# SCH_MIW_PS_on_PCB_2022-01-19.net
KiCad netlist of a schematic drawn in EasyEDA
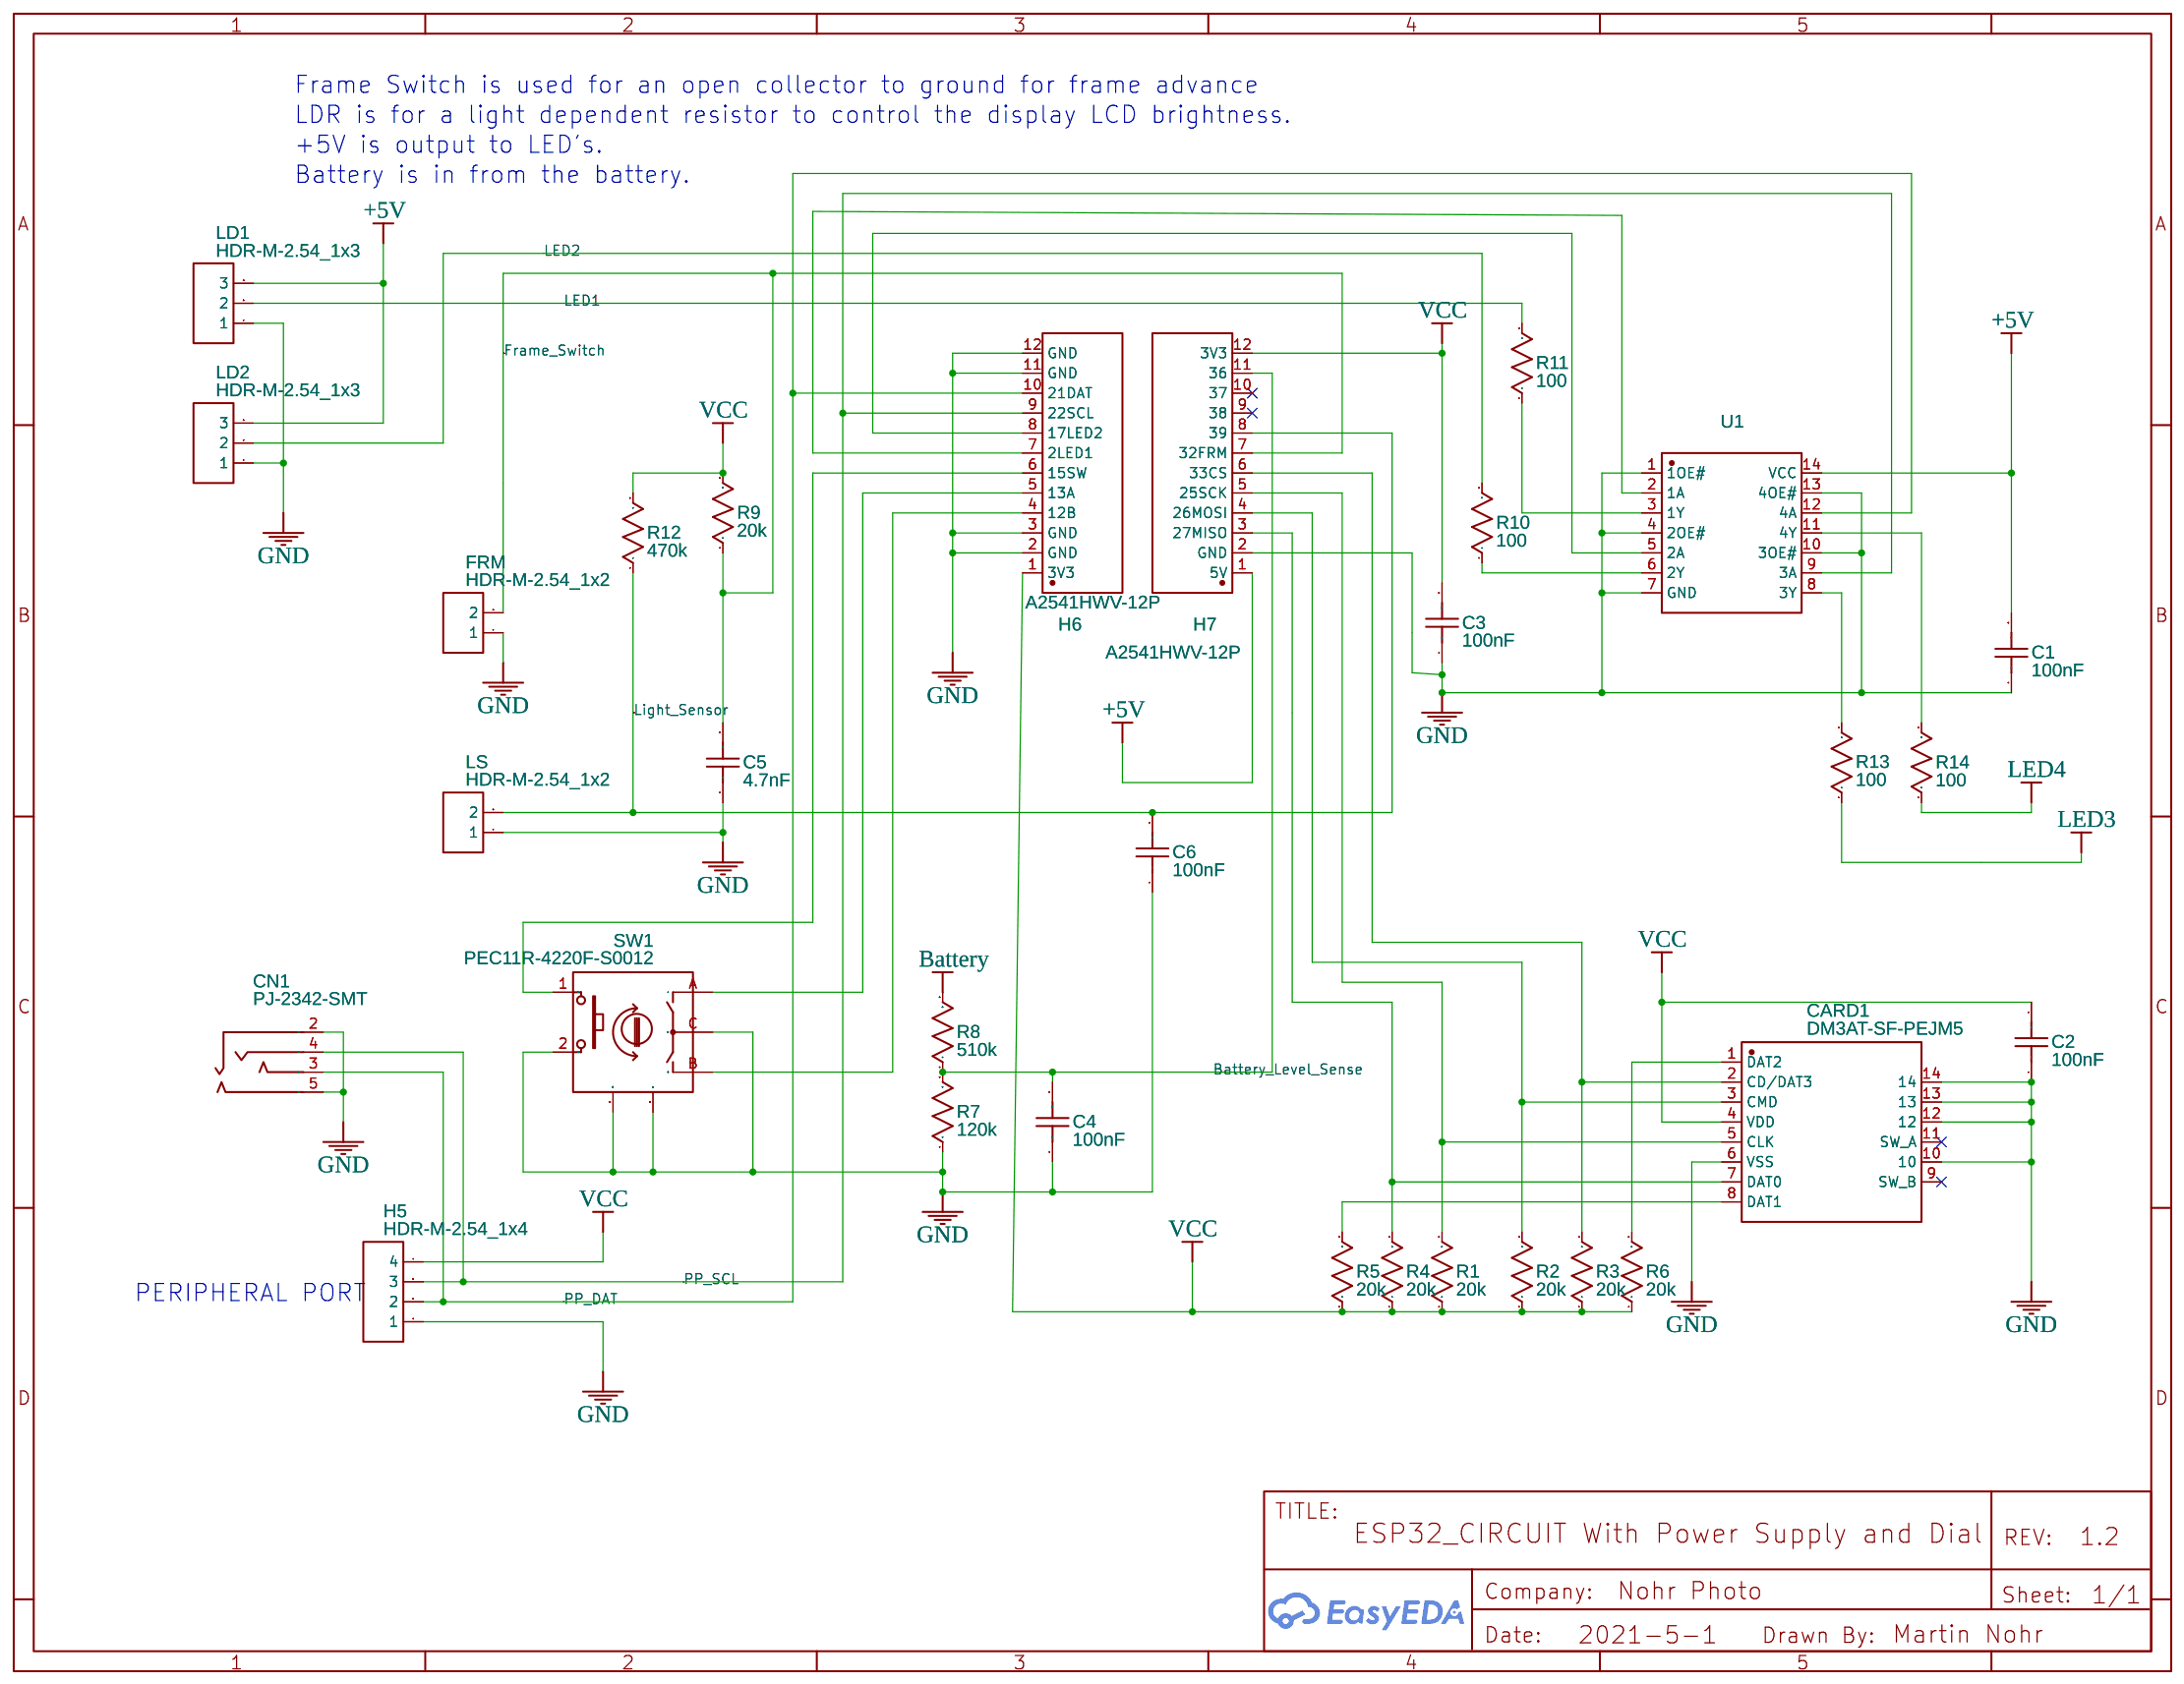
[diagram p0: TTGO_CIRCUIT_PCB_UNIFIED]
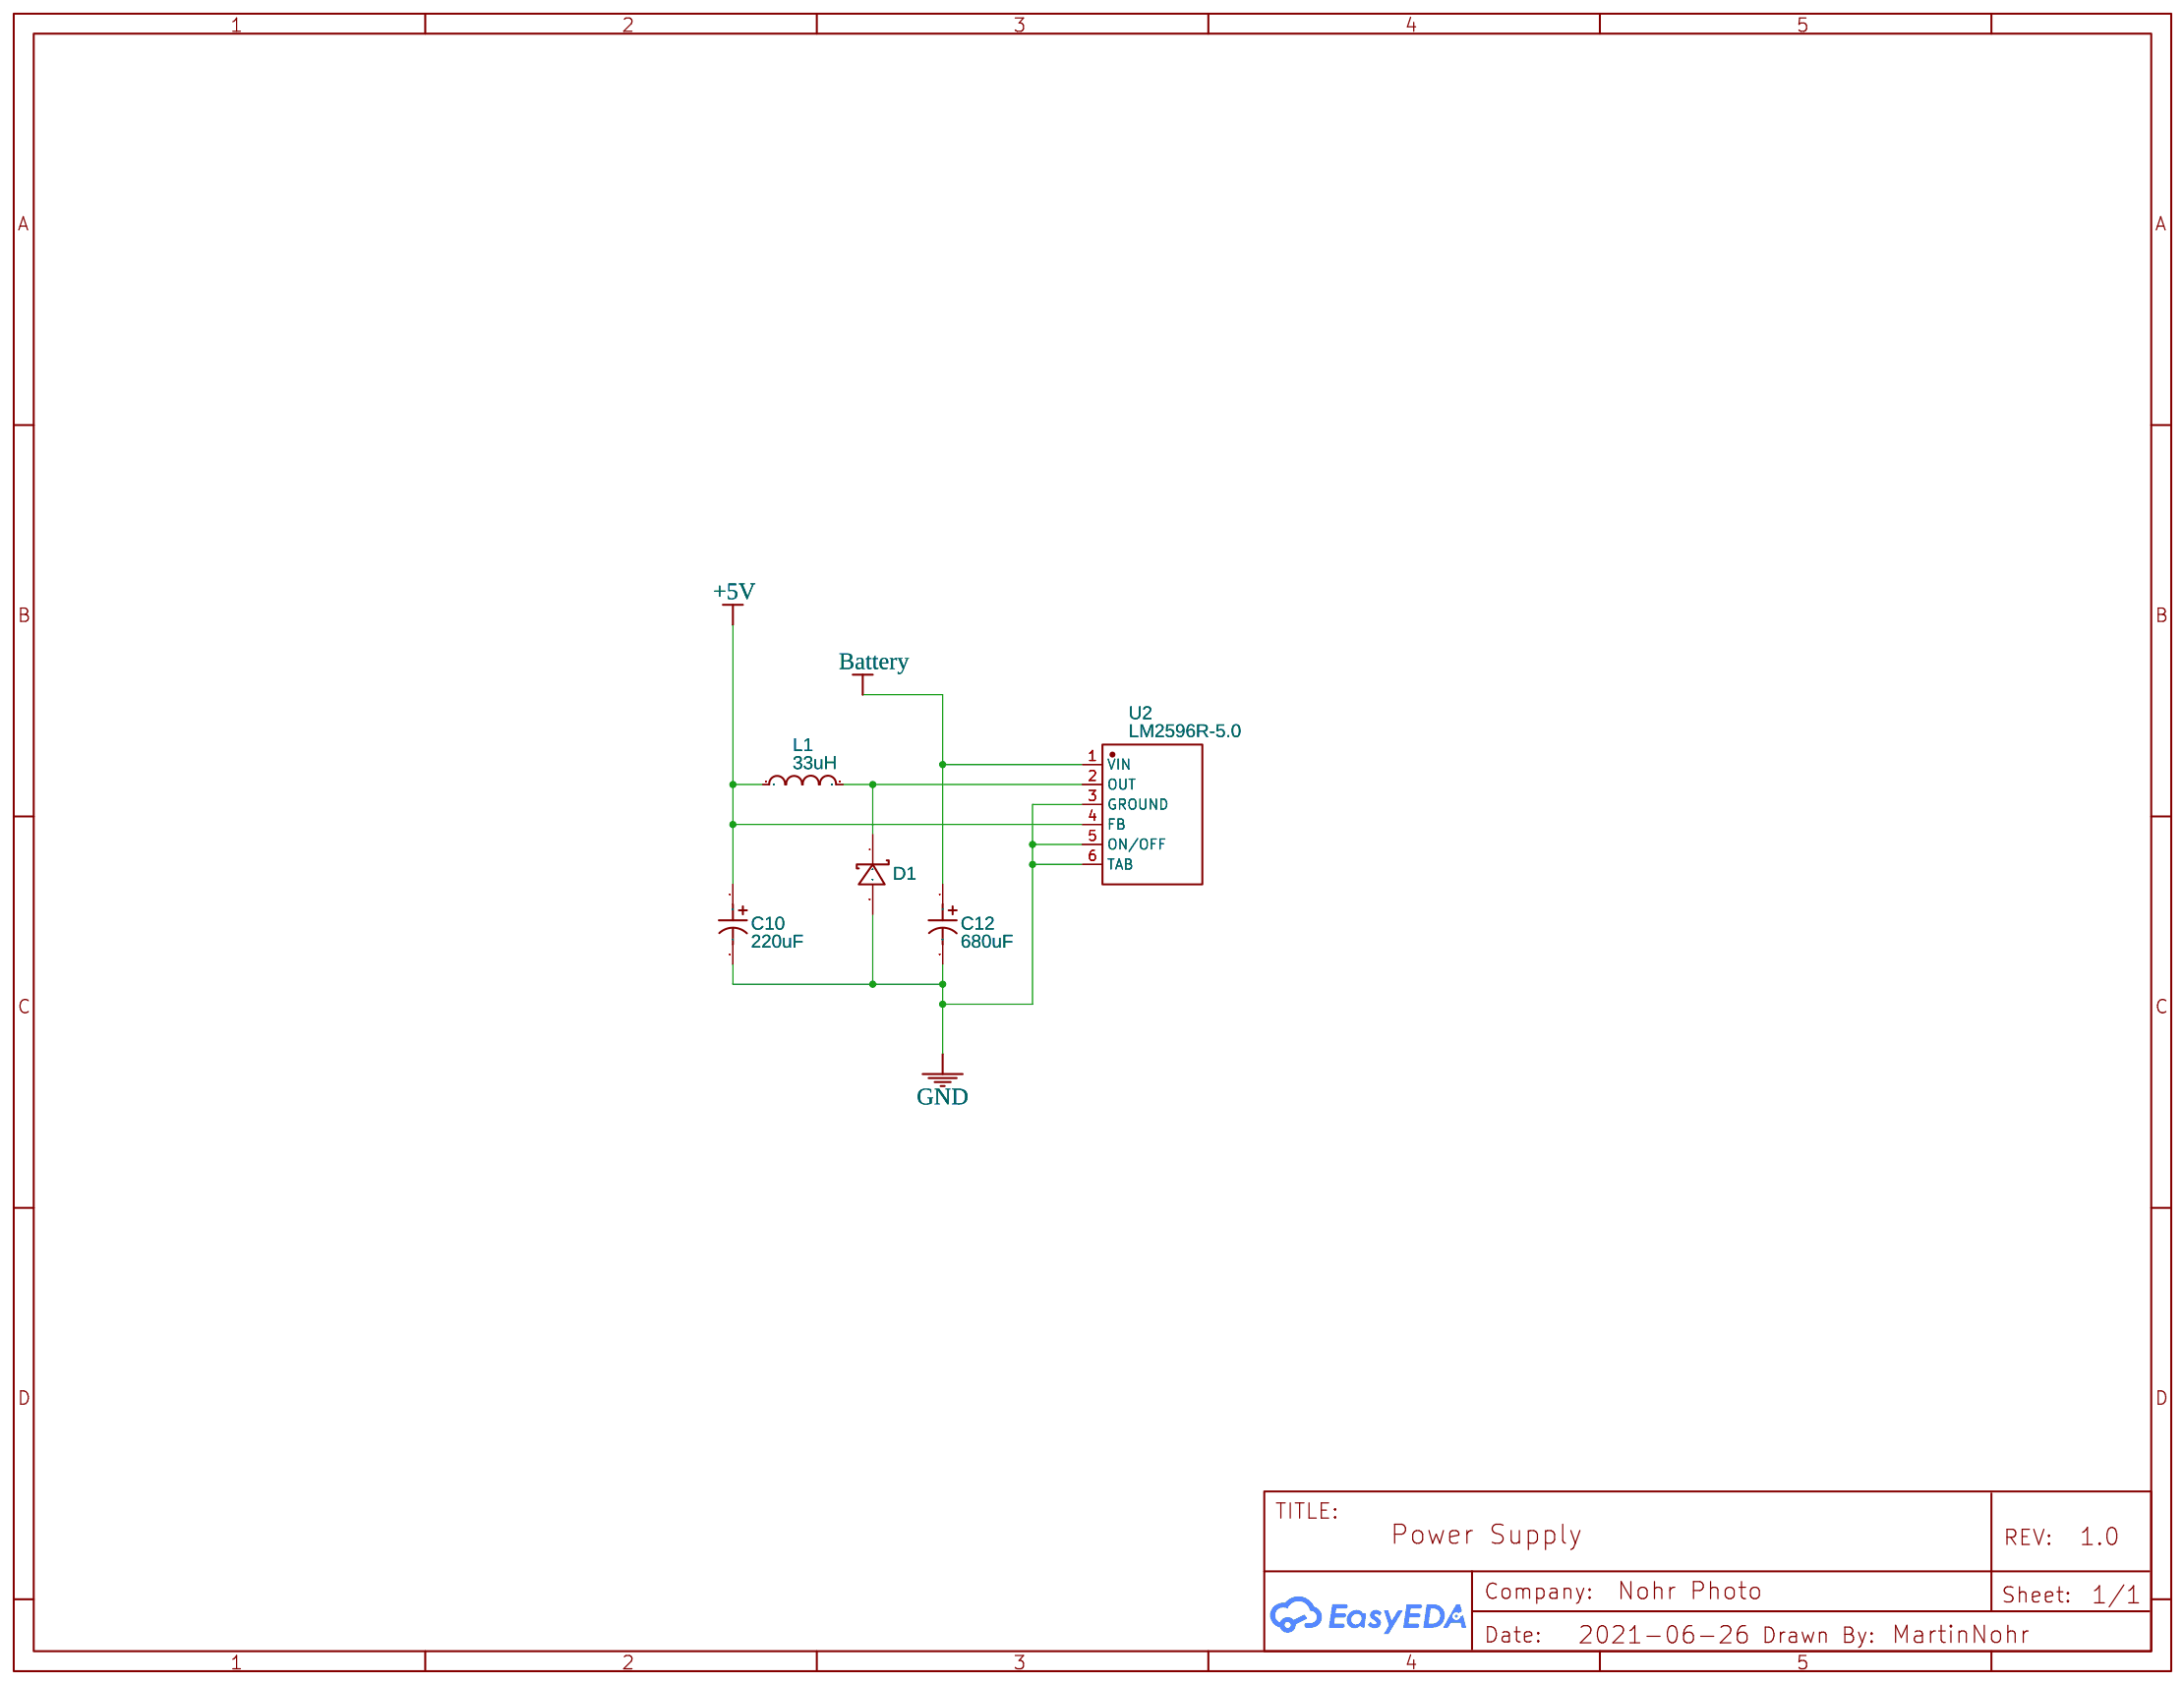
[diagram p1: Power Supply Circuit]

(export (version "E")
  (design (tool "Eeschema 10.0.6"))
  (components
    (comp (ref "C1")
      (value "100nF")
      (fields
        (field (name "BOM_Manufacturer Part") "CL10B104KC8NNNC")
        (field (name "BOM_Supplier Part") "C15725")
      )
      (libsource (lib "") (part "CL10B104KB8NFNC"))
    )
    (comp (ref "C2")
      (value "100nF")
      (fields
        (field (name "BOM_Manufacturer Part") "CL10B104KC8NNNC")
        (field (name "BOM_Supplier Part") "C15725")
      )
      (libsource (lib "") (part "CL10B104KB8NFNC"))
    )
    (comp (ref "C3")
      (value "100nF")
      (fields
        (field (name "BOM_Manufacturer Part") "CL10B104KC8NNNC")
        (field (name "BOM_Supplier Part") "C15725")
      )
      (libsource (lib "") (part "CL10B104KB8NFNC"))
    )
    (comp (ref "C4")
      (value "100nF")
      (fields
        (field (name "BOM_Manufacturer Part") "CL10B104KC8NNNC")
        (field (name "BOM_Supplier Part") "C15725")
      )
      (libsource (lib "") (part "CL10B104KB8NFNC"))
    )
    (comp (ref "C5")
      (value "4.7nF")
      (fields
        (field (name "BOM_Manufacturer Part") "CC0603KRX7R9BB472")
        (field (name "BOM_Supplier Part") "C106218")
      )
      (libsource (lib "") (part "CL10B104KB8NFNC"))
    )
    (comp (ref "C6")
      (value "100nF")
      (fields
        (field (name "BOM_Manufacturer Part") "CL10B104KC8NNNC")
        (field (name "BOM_Supplier Part") "C15725")
      )
      (libsource (lib "") (part "CL10B104KB8NFNC"))
    )
    (comp (ref "CARD1")
      (value "DM3AT-SF-PEJM5")
      (fields (field (name "BOM_Supplier Part") "C114218"))
      (libsource (lib "") (part "DM3AT-SF-PEJM5"))
    )
    (comp (ref "CN1")
      (value "PJ-2342-SMT")
      (fields (field (name "BOM_Supplier Part") "C397356"))
      (libsource (lib "") (part "PJ-2342-SMT"))
    )
    (comp (ref "FRM")
      (value "HDR-M-2.54_1x2")
      (fields (field (name "BOM_Supplier Part") "C124375"))
      (libsource (lib "") (part "HDR-M-2.54_1x2_1"))
    )
    (comp (ref "H5")
      (value "HDR-M-2.54_1x4")
      (fields (field (name "BOM_Supplier Part") "C124378"))
      (libsource (lib "") (part "HDR-F-2.54_1x4"))
    )
    (comp (ref "H6")
      (value "A2541HWV-12P")
      (fields (field (name "BOM_Supplier Part") "C225509"))
      (libsource (lib "") (part "A2541HWV-12P_1"))
    )
    (comp (ref "H7")
      (value "A2541HWV-12P")
      (fields (field (name "BOM_Supplier Part") "C225509"))
      (libsource (lib "") (part "A2541HWV-12P"))
    )
    (comp (ref "LD1")
      (value "HDR-M-2.54_1x3")
      (fields (field (name "BOM_Supplier Part") "C180248"))
      (libsource (lib "") (part "HDR-M-2.54_1x3"))
    )
    (comp (ref "LD2")
      (value "HDR-M-2.54_1x3")
      (fields (field (name "BOM_Supplier Part") "C180248"))
      (libsource (lib "") (part "HDR-M-2.54_1x3"))
    )
    (comp (ref "LS")
      (value "HDR-M-2.54_1x2")
      (fields (field (name "BOM_Supplier Part") "C124375"))
      (libsource (lib "") (part "HDR-M-2.54_1x2"))
    )
    (comp (ref "R1")
      (value "20k")
      (fields
        (field (name "BOM_Manufacturer Part") "0603WAF2002T5E")
        (field (name "BOM_Supplier Part") "C4184")
      )
      (libsource (lib "") (part "R_0603_US"))
    )
    (comp (ref "R2")
      (value "20k")
      (fields
        (field (name "BOM_Manufacturer Part") "0603WAF2002T5E")
        (field (name "BOM_Supplier Part") "C4184")
      )
      (libsource (lib "") (part "R_0603_US"))
    )
    (comp (ref "R3")
      (value "20k")
      (fields
        (field (name "BOM_Manufacturer Part") "0603WAF2002T5E")
        (field (name "BOM_Supplier Part") "C4184")
      )
      (libsource (lib "") (part "R_0603_US"))
    )
    (comp (ref "R4")
      (value "20k")
      (fields
        (field (name "BOM_Manufacturer Part") "0603WAF2002T5E")
        (field (name "BOM_Supplier Part") "C4184")
      )
      (libsource (lib "") (part "R_0603_US"))
    )
    (comp (ref "R5")
      (value "20k")
      (fields
        (field (name "BOM_Manufacturer Part") "0603WAF2002T5E")
        (field (name "BOM_Supplier Part") "C4184")
      )
      (libsource (lib "") (part "R_0603_US"))
    )
    (comp (ref "R6")
      (value "20k")
      (fields
        (field (name "BOM_Manufacturer Part") "0603WAF2002T5E")
        (field (name "BOM_Supplier Part") "C4184")
      )
      (libsource (lib "") (part "R_0603_US"))
    )
    (comp (ref "R7")
      (value "120k")
      (fields
        (field (name "BOM_Manufacturer Part") "0603WAF1203T5E")
        (field (name "BOM_Supplier Part") "C25808")
      )
      (libsource (lib "") (part "R_0603_US"))
    )
    (comp (ref "R8")
      (value "510k")
      (fields
        (field (name "BOM_Manufacturer Part") "0603WAF5103T5E")
        (field (name "BOM_Supplier Part") "C23192")
      )
      (libsource (lib "") (part "R_0603_US"))
    )
    (comp (ref "R9")
      (value "20k")
      (fields
        (field (name "BOM_Manufacturer Part") "0603WAF2002T5E")
        (field (name "BOM_Supplier Part") "C4184")
      )
      (libsource (lib "") (part "R_0603_US"))
    )
    (comp (ref "R10")
      (value "100")
      (fields
        (field (name "BOM_Manufacturer Part") "0603WAF1000T5E")
        (field (name "BOM_Supplier Part") "C22775")
      )
      (libsource (lib "") (part "R_0603_US"))
    )
    (comp (ref "R11")
      (value "100")
      (fields
        (field (name "BOM_Manufacturer Part") "0603WAF1000T5E")
        (field (name "BOM_Supplier Part") "C22775")
      )
      (libsource (lib "") (part "R_0603_US"))
    )
    (comp (ref "R12")
      (value "470k")
      (fields
        (field (name "BOM_Manufacturer Part") "0603WAF4703T5E")
        (field (name "BOM_Supplier Part") "C23178")
      )
      (libsource (lib "") (part "R_0603_US"))
    )
    (comp (ref "R13")
      (value "100")
      (fields
        (field (name "BOM_Manufacturer Part") "0603WAF1000T5E")
        (field (name "BOM_Supplier Part") "C22775")
      )
      (libsource (lib "") (part "R_0603_US"))
    )
    (comp (ref "R14")
      (value "100")
      (fields
        (field (name "BOM_Manufacturer Part") "0603WAF1000T5E")
        (field (name "BOM_Supplier Part") "C22775")
      )
      (libsource (lib "") (part "R_0603_US"))
    )
    (comp (ref "SW1")
      (value "PEC11R-4220F-S0012")
      (fields (field (name "BOM_Supplier Part") "C143817"))
      (libsource (lib "") (part "PEC11R-4015F-S0024"))
    )
    (comp (ref "U1")
      (value "74HCT125PW,112")
      (fields (field (name "BOM_Supplier Part") "C545657"))
      (libsource (lib "") (part "74HCT125PW,112"))
    )
    (comp (ref "C10")
      (value "220uF")
      (fields
        (field (name "BOM_Manufacturer Part") "KS227M016E07RR0VH2FP0")
        (field (name "BOM_Supplier Part") "C43340")
      )
      (libsource (lib "") (part "160ARCP221M05X8P00"))
    )
    (comp (ref "C12")
      (value "680uF")
      (fields
        (field (name "BOM_Manufacturer Part") "SPT1EM681F12OR")
        (field (name "BOM_Supplier Part") "C698148")
      )
      (libsource (lib "") (part "SPT1EM681F12OR"))
    )
    (comp (ref "D1")
      (value "B2100-13-F")
      (fields (field (name "BOM_Supplier Part") "C110479"))
      (libsource (lib "") (part "B2100-13-F"))
    )
    (comp (ref "L1")
      (value "33uH")
      (fields
        (field (name "BOM_Manufacturer Part") "YSPI1050-330M")
        (field (name "BOM_Supplier Part") "C497900")
      )
      (libsource (lib "") (part "YSPI1050-330M"))
    )
    (comp (ref "U2")
      (value "LM2596R-5.0")
      (fields (field (name "BOM_Supplier Part") "C77782"))
      (libsource (lib "") (part "LM2596R-5.0"))
    )
  )
  (nets
    (net (code "1") (name "+5V") (class "Default")
      (node (ref "C1") (pin "2") (pinfunction "2_2") (pintype "unspecified"))
      (node (ref "C10") (pin "1") (pinfunction "1_1") (pintype "input"))
      (node (ref "H7") (pin "1") (pinfunction "5V_1") (pintype "unspecified"))
      (node (ref "L1") (pin "1") (pinfunction "1_1") (pintype "unspecified"))
      (node (ref "LD1") (pin "3") (pinfunction "3_3") (pintype "input"))
      (node (ref "LD2") (pin "3") (pinfunction "3_3") (pintype "input"))
      (node (ref "U1") (pin "14") (pinfunction "VCC_14") (pintype "unspecified"))
      (node (ref "U2") (pin "4") (pinfunction "FB_4") (pintype "unspecified"))
    )
    (net (code "2") (name "Battery") (class "Default")
      (node (ref "C12") (pin "1") (pinfunction "1_1") (pintype "input"))
      (node (ref "R8") (pin "2") (pinfunction "2_2") (pintype "unspecified"))
      (node (ref "U2") (pin "1") (pinfunction "VIN_1") (pintype "unspecified"))
    )
    (net (code "3") (name "Battery_Level_Sense") (class "Default")
      (node (ref "C4") (pin "2") (pinfunction "2_2") (pintype "unspecified"))
      (node (ref "H7") (pin "11") (pinfunction "36_11") (pintype "unspecified"))
      (node (ref "R7") (pin "2") (pinfunction "2_2") (pintype "unspecified"))
      (node (ref "R8") (pin "1") (pinfunction "1_1") (pintype "unspecified"))
    )
    (net (code "4") (name "Frame_Switch") (class "Default")
      (node (ref "C5") (pin "2") (pinfunction "2_2") (pintype "unspecified"))
      (node (ref "FRM") (pin "2") (pinfunction "2_2") (pintype "unspecified"))
      (node (ref "H7") (pin "7") (pinfunction "32FRM_7") (pintype "unspecified"))
      (node (ref "R9") (pin "1") (pinfunction "1_1") (pintype "unspecified"))
    )
    (net (code "5") (name "GND") (class "Default")
      (node (ref "C1") (pin "1") (pinfunction "1_1") (pintype "unspecified"))
      (node (ref "C10") (pin "2") (pinfunction "2_2") (pintype "input"))
      (node (ref "C12") (pin "2") (pinfunction "2_2") (pintype "input"))
      (node (ref "C2") (pin "1") (pinfunction "1_1") (pintype "unspecified"))
      (node (ref "C3") (pin "1") (pinfunction "1_1") (pintype "unspecified"))
      (node (ref "C4") (pin "1") (pinfunction "1_1") (pintype "unspecified"))
      (node (ref "C5") (pin "1") (pinfunction "1_1") (pintype "unspecified"))
      (node (ref "C6") (pin "1") (pinfunction "1_1") (pintype "unspecified"))
      (node (ref "CARD1") (pin "10") (pinfunction "10_10") (pintype "unspecified"))
      (node (ref "CARD1") (pin "12") (pinfunction "12_12") (pintype "unspecified"))
      (node (ref "CARD1") (pin "13") (pinfunction "13_13") (pintype "unspecified"))
      (node (ref "CARD1") (pin "14") (pinfunction "14_14") (pintype "unspecified"))
      (node (ref "CARD1") (pin "6") (pinfunction "VSS_6") (pintype "unspecified"))
      (node (ref "CN1") (pin "2") (pinfunction "2_2") (pintype "unspecified"))
      (node (ref "CN1") (pin "5") (pinfunction "5_5") (pintype "unspecified"))
      (node (ref "D1") (pin "2") (pinfunction "2_2") (pintype "unspecified"))
      (node (ref "FRM") (pin "1") (pinfunction "1_1") (pintype "unspecified"))
      (node (ref "H5") (pin "1") (pinfunction "1_1") (pintype "unspecified"))
      (node (ref "H6") (pin "11") (pinfunction "GND_11") (pintype "unspecified"))
      (node (ref "H6") (pin "12") (pinfunction "GND_12") (pintype "unspecified"))
      (node (ref "H6") (pin "2") (pinfunction "GND_2") (pintype "unspecified"))
      (node (ref "H6") (pin "3") (pinfunction "GND_3") (pintype "unspecified"))
      (node (ref "H7") (pin "2") (pinfunction "GND_2") (pintype "unspecified"))
      (node (ref "LD1") (pin "1") (pinfunction "1_1") (pintype "input"))
      (node (ref "LD2") (pin "1") (pinfunction "1_1") (pintype "input"))
      (node (ref "LS") (pin "1") (pinfunction "1_1") (pintype "unspecified"))
      (node (ref "R7") (pin "1") (pinfunction "1_1") (pintype "unspecified"))
      (node (ref "SW1") (pin "2") (pinfunction "2_2") (pintype "unspecified"))
      (node (ref "SW1") (pin "C") (pinfunction "C_C") (pintype "unspecified"))
      (node (ref "SW1") (pin "MT1") (pinfunction "MT1_MT1") (pintype "unspecified"))
      (node (ref "SW1") (pin "MT2") (pinfunction "MT2_MT2") (pintype "unspecified"))
      (node (ref "U1") (pin "1") (pinfunction "1OE#_1") (pintype "unspecified"))
      (node (ref "U1") (pin "10") (pinfunction "3OE#_10") (pintype "unspecified"))
      (node (ref "U1") (pin "13") (pinfunction "4OE#_13") (pintype "unspecified"))
      (node (ref "U1") (pin "4") (pinfunction "2OE#_4") (pintype "unspecified"))
      (node (ref "U1") (pin "7") (pinfunction "GND_7") (pintype "unspecified"))
      (node (ref "U2") (pin "3") (pinfunction "GROUND_3") (pintype "unspecified"))
      (node (ref "U2") (pin "5") (pinfunction "ON/OFF_5") (pintype "unspecified"))
      (node (ref "U2") (pin "6") (pinfunction "TAB_6") (pintype "unspecified"))
    )
    (net (code "6") (name "LED1") (class "Default")
      (node (ref "LD1") (pin "2") (pinfunction "2_2") (pintype "input"))
      (node (ref "R11") (pin "2") (pinfunction "2_2") (pintype "unspecified"))
    )
    (net (code "7") (name "LED2") (class "Default")
      (node (ref "LD2") (pin "2") (pinfunction "2_2") (pintype "input"))
      (node (ref "R10") (pin "2") (pinfunction "2_2") (pintype "unspecified"))
    )
    (net (code "8") (name "LED3") (class "Default")
      (node (ref "R13") (pin "1") (pinfunction "1_1") (pintype "unspecified"))
    )
    (net (code "9") (name "LED4") (class "Default")
      (node (ref "R14") (pin "1") (pinfunction "1_1") (pintype "unspecified"))
    )
    (net (code "10") (name "Light_Sensor") (class "Default")
      (node (ref "C6") (pin "2") (pinfunction "2_2") (pintype "unspecified"))
      (node (ref "H7") (pin "8") (pinfunction "39_8") (pintype "unspecified"))
      (node (ref "LS") (pin "2") (pinfunction "2_2") (pintype "unspecified"))
      (node (ref "R12") (pin "1") (pinfunction "1_1") (pintype "unspecified"))
    )
    (net (code "11") (name "Net-(CARD1-CD{slash}DAT3)") (class "Default")
      (node (ref "CARD1") (pin "2") (pinfunction "CD/DAT3_2") (pintype "unspecified"))
      (node (ref "H7") (pin "6") (pinfunction "33CS_6") (pintype "unspecified"))
      (node (ref "R3") (pin "2") (pinfunction "2_2") (pintype "unspecified"))
    )
    (net (code "12") (name "Net-(CARD1-CLK)") (class "Default")
      (node (ref "CARD1") (pin "5") (pinfunction "CLK_5") (pintype "unspecified"))
      (node (ref "H7") (pin "5") (pinfunction "25SCK_5") (pintype "unspecified"))
      (node (ref "R1") (pin "2") (pinfunction "2_2") (pintype "unspecified"))
    )
    (net (code "13") (name "Net-(CARD1-CMD)") (class "Default")
      (node (ref "CARD1") (pin "3") (pinfunction "CMD_3") (pintype "unspecified"))
      (node (ref "H7") (pin "4") (pinfunction "26MOSI_4") (pintype "unspecified"))
      (node (ref "R2") (pin "2") (pinfunction "2_2") (pintype "unspecified"))
    )
    (net (code "14") (name "Net-(CARD1-DAT0)") (class "Default")
      (node (ref "CARD1") (pin "7") (pinfunction "DAT0_7") (pintype "unspecified"))
      (node (ref "H7") (pin "3") (pinfunction "27MISO_3") (pintype "unspecified"))
      (node (ref "R4") (pin "2") (pinfunction "2_2") (pintype "unspecified"))
    )
    (net (code "15") (name "Net-(CARD1-DAT1)") (class "Default")
      (node (ref "CARD1") (pin "8") (pinfunction "DAT1_8") (pintype "unspecified"))
      (node (ref "R5") (pin "2") (pinfunction "2_2") (pintype "unspecified"))
    )
    (net (code "16") (name "Net-(CARD1-DAT2)") (class "Default")
      (node (ref "CARD1") (pin "1") (pinfunction "DAT2_1") (pintype "unspecified"))
      (node (ref "R6") (pin "2") (pinfunction "2_2") (pintype "unspecified"))
    )
    (net (code "17") (name "Net-(H6-2LED1)") (class "Default")
      (node (ref "H6") (pin "7") (pinfunction "2LED1_7") (pintype "unspecified"))
      (node (ref "U1") (pin "2") (pinfunction "1A_2") (pintype "unspecified"))
    )
    (net (code "18") (name "Net-(H6-12B)") (class "Default")
      (node (ref "H6") (pin "4") (pinfunction "12B_4") (pintype "unspecified"))
      (node (ref "SW1") (pin "B") (pinfunction "B_B") (pintype "unspecified"))
    )
    (net (code "19") (name "Net-(H6-13A)") (class "Default")
      (node (ref "H6") (pin "5") (pinfunction "13A_5") (pintype "unspecified"))
      (node (ref "SW1") (pin "A") (pinfunction "A_A") (pintype "unspecified"))
    )
    (net (code "20") (name "Net-(H6-15SW)") (class "Default")
      (node (ref "H6") (pin "6") (pinfunction "15SW_6") (pintype "unspecified"))
      (node (ref "SW1") (pin "1") (pinfunction "1_1") (pintype "unspecified"))
    )
    (net (code "21") (name "Net-(H6-17LED2)") (class "Default")
      (node (ref "H6") (pin "8") (pinfunction "17LED2_8") (pintype "unspecified"))
      (node (ref "U1") (pin "5") (pinfunction "2A_5") (pintype "unspecified"))
    )
    (net (code "22") (name "Net-(U1-1Y)") (class "Default")
      (node (ref "R11") (pin "1") (pinfunction "1_1") (pintype "unspecified"))
      (node (ref "U1") (pin "3") (pinfunction "1Y_3") (pintype "unspecified"))
    )
    (net (code "23") (name "Net-(U1-2Y)") (class "Default")
      (node (ref "R10") (pin "1") (pinfunction "1_1") (pintype "unspecified"))
      (node (ref "U1") (pin "6") (pinfunction "2Y_6") (pintype "unspecified"))
    )
    (net (code "24") (name "Net-(U1-3Y)") (class "Default")
      (node (ref "R13") (pin "2") (pinfunction "2_2") (pintype "unspecified"))
      (node (ref "U1") (pin "8") (pinfunction "3Y_8") (pintype "unspecified"))
    )
    (net (code "25") (name "Net-(U1-4Y)") (class "Default")
      (node (ref "R14") (pin "2") (pinfunction "2_2") (pintype "unspecified"))
      (node (ref "U1") (pin "11") (pinfunction "4Y_11") (pintype "unspecified"))
    )
    (net (code "26") (name "Net-(U2-OUT)") (class "Default")
      (node (ref "D1") (pin "1") (pinfunction "1_1") (pintype "unspecified"))
      (node (ref "L1") (pin "2") (pinfunction "2_2") (pintype "unspecified"))
      (node (ref "U2") (pin "2") (pinfunction "OUT_2") (pintype "unspecified"))
    )
    (net (code "27") (name "PP_DAT") (class "Default")
      (node (ref "CN1") (pin "3") (pinfunction "3_3") (pintype "unspecified"))
      (node (ref "H5") (pin "2") (pinfunction "2_2") (pintype "unspecified"))
      (node (ref "H6") (pin "10") (pinfunction "21DAT_10") (pintype "unspecified"))
      (node (ref "U1") (pin "12") (pinfunction "4A_12") (pintype "unspecified"))
    )
    (net (code "28") (name "PP_SCL") (class "Default")
      (node (ref "CN1") (pin "4") (pinfunction "4_4") (pintype "unspecified"))
      (node (ref "H5") (pin "3") (pinfunction "3_3") (pintype "unspecified"))
      (node (ref "H6") (pin "9") (pinfunction "22SCL_9") (pintype "unspecified"))
      (node (ref "U1") (pin "9") (pinfunction "3A_9") (pintype "unspecified"))
    )
    (net (code "29") (name "VCC") (class "Default")
      (node (ref "C2") (pin "2") (pinfunction "2_2") (pintype "unspecified"))
      (node (ref "C3") (pin "2") (pinfunction "2_2") (pintype "unspecified"))
      (node (ref "CARD1") (pin "4") (pinfunction "VDD_4") (pintype "unspecified"))
      (node (ref "H5") (pin "4") (pinfunction "4_4") (pintype "unspecified"))
      (node (ref "H6") (pin "1") (pinfunction "3V3_1") (pintype "unspecified"))
      (node (ref "H7") (pin "12") (pinfunction "3V3_12") (pintype "unspecified"))
      (node (ref "R1") (pin "1") (pinfunction "1_1") (pintype "unspecified"))
      (node (ref "R12") (pin "2") (pinfunction "2_2") (pintype "unspecified"))
      (node (ref "R2") (pin "1") (pinfunction "1_1") (pintype "unspecified"))
      (node (ref "R3") (pin "1") (pinfunction "1_1") (pintype "unspecified"))
      (node (ref "R4") (pin "1") (pinfunction "1_1") (pintype "unspecified"))
      (node (ref "R5") (pin "1") (pinfunction "1_1") (pintype "unspecified"))
      (node (ref "R6") (pin "1") (pinfunction "1_1") (pintype "unspecified"))
      (node (ref "R9") (pin "2") (pinfunction "2_2") (pintype "unspecified"))
    )
    (net (code "30") (name "unconnected-(CARD1-SW_A-Pad11)") (class "Default")
      (node (ref "CARD1") (pin "11") (pinfunction "SW_A_11") (pintype "unspecified+no_connect"))
    )
    (net (code "31") (name "unconnected-(CARD1-SW_B-Pad9)") (class "Default")
      (node (ref "CARD1") (pin "9") (pinfunction "SW_B_9") (pintype "unspecified+no_connect"))
    )
    (net (code "32") (name "unconnected-(H7-37-Pad10)") (class "Default")
      (node (ref "H7") (pin "10") (pinfunction "37_10") (pintype "unspecified+no_connect"))
    )
    (net (code "33") (name "unconnected-(H7-38-Pad9)") (class "Default")
      (node (ref "H7") (pin "9") (pinfunction "38_9") (pintype "unspecified+no_connect"))
    )
  )
)
